# Output_v1_1.net
KiCad netlist of a schematic drawn in EAGLE
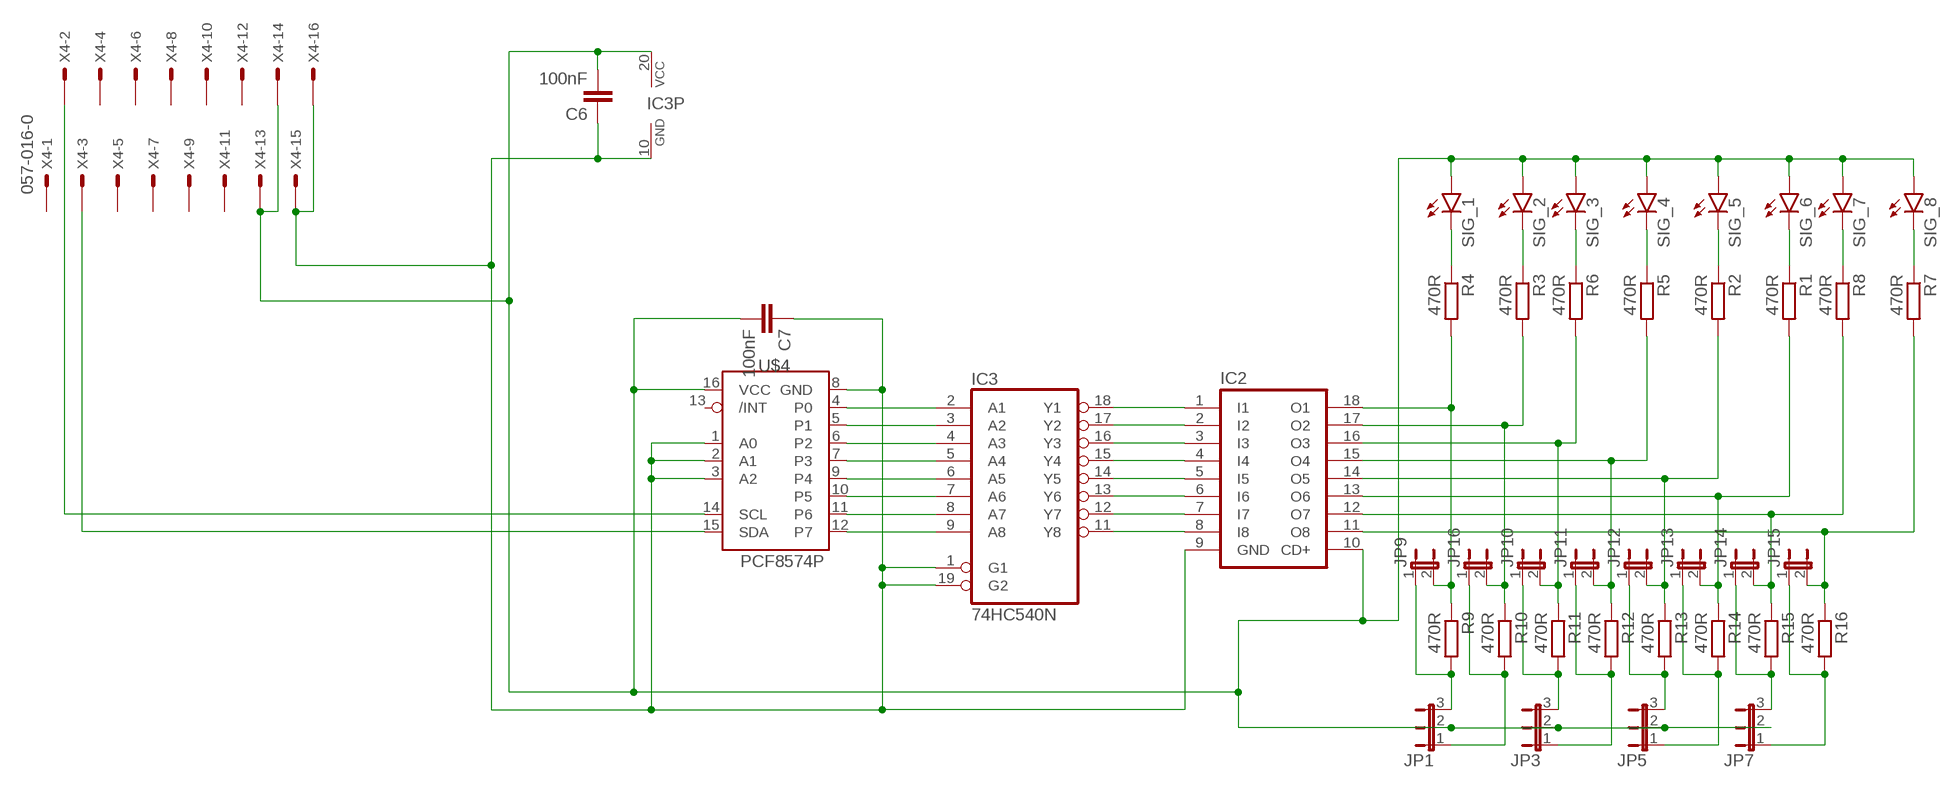
[diagram p0: schematic, sheet 1]

(export (version "E")
  (design (tool "Eeschema 10.0.6"))
  (components
    (comp (ref "C6")
      (value "100nF")
      (footprint "eagle-import:C025-024X044")
      (libsource (lib "eagle-import") (part "C-EU025-024X044"))
    )
    (comp (ref "C7")
      (value "100nF")
      (footprint "eagle-import:C025-024X044")
      (libsource (lib "eagle-import") (part "C-EU025-024X044"))
    )
    (comp (ref "IC2")
      (value "ULN2803A")
      (footprint "eagle-import:DIL18")
      (libsource (lib "eagle-import") (part "ULN2803A"))
    )
    (comp (ref "IC3")
      (value "74HC540N")
      (footprint "eagle-import:DIL20")
      (libsource (lib "eagle-import") (part "74540NHC"))
    )
    (comp (ref "JP1")
      (value "JP2E")
      (footprint "eagle-import:JP2")
      (libsource (lib "eagle-import") (part "JP2E"))
    )
    (comp (ref "JP3")
      (value "JP2E")
      (footprint "eagle-import:JP2")
      (libsource (lib "eagle-import") (part "JP2E"))
    )
    (comp (ref "JP5")
      (value "JP2E")
      (footprint "eagle-import:JP2")
      (libsource (lib "eagle-import") (part "JP2E"))
    )
    (comp (ref "JP7")
      (value "JP2E")
      (footprint "eagle-import:JP2")
      (libsource (lib "eagle-import") (part "JP2E"))
    )
    (comp (ref "JP9")
      (value "JP1E")
      (footprint "eagle-import:JP1")
      (libsource (lib "eagle-import") (part "JP1E"))
    )
    (comp (ref "JP10")
      (value "JP1E")
      (footprint "eagle-import:JP1")
      (libsource (lib "eagle-import") (part "JP1E"))
    )
    (comp (ref "JP11")
      (value "JP1E")
      (footprint "eagle-import:JP1")
      (libsource (lib "eagle-import") (part "JP1E"))
    )
    (comp (ref "JP12")
      (value "JP1E")
      (footprint "eagle-import:JP1")
      (libsource (lib "eagle-import") (part "JP1E"))
    )
    (comp (ref "JP13")
      (value "JP1E")
      (footprint "eagle-import:JP1")
      (libsource (lib "eagle-import") (part "JP1E"))
    )
    (comp (ref "JP14")
      (value "JP1E")
      (footprint "eagle-import:JP1")
      (libsource (lib "eagle-import") (part "JP1E"))
    )
    (comp (ref "JP15")
      (value "JP1E")
      (footprint "eagle-import:JP1")
      (libsource (lib "eagle-import") (part "JP1E"))
    )
    (comp (ref "JP16")
      (value "JP1E")
      (footprint "eagle-import:JP1")
      (libsource (lib "eagle-import") (part "JP1E"))
    )
    (comp (ref "R1")
      (value "470R")
      (footprint "eagle-import:0309_10")
      (libsource (lib "eagle-import") (part "R-EU_0309/10"))
    )
    (comp (ref "R2")
      (value "470R")
      (footprint "eagle-import:0309_10")
      (libsource (lib "eagle-import") (part "R-EU_0309/10"))
    )
    (comp (ref "R3")
      (value "470R")
      (footprint "eagle-import:0309_10")
      (libsource (lib "eagle-import") (part "R-EU_0309/10"))
    )
    (comp (ref "R4")
      (value "470R")
      (footprint "eagle-import:0309_10")
      (libsource (lib "eagle-import") (part "R-EU_0309/10"))
    )
    (comp (ref "R5")
      (value "470R")
      (footprint "eagle-import:0309_10")
      (libsource (lib "eagle-import") (part "R-EU_0309/10"))
    )
    (comp (ref "R6")
      (value "470R")
      (footprint "eagle-import:0309_10")
      (libsource (lib "eagle-import") (part "R-EU_0309/10"))
    )
    (comp (ref "R7")
      (value "470R")
      (footprint "eagle-import:0309_10")
      (libsource (lib "eagle-import") (part "R-EU_0309/10"))
    )
    (comp (ref "R8")
      (value "470R")
      (footprint "eagle-import:0309_10")
      (libsource (lib "eagle-import") (part "R-EU_0309/10"))
    )
    (comp (ref "R9")
      (value "470R")
      (footprint "eagle-import:0309_10")
      (libsource (lib "eagle-import") (part "R-EU_0309/10"))
    )
    (comp (ref "R10")
      (value "470R")
      (footprint "eagle-import:0309_10")
      (libsource (lib "eagle-import") (part "R-EU_0309/10"))
    )
    (comp (ref "R11")
      (value "470R")
      (footprint "eagle-import:0309_10")
      (libsource (lib "eagle-import") (part "R-EU_0309/10"))
    )
    (comp (ref "R12")
      (value "470R")
      (footprint "eagle-import:0309_10")
      (libsource (lib "eagle-import") (part "R-EU_0309/10"))
    )
    (comp (ref "R13")
      (value "470R")
      (footprint "eagle-import:0309_10")
      (libsource (lib "eagle-import") (part "R-EU_0309/10"))
    )
    (comp (ref "R14")
      (value "470R")
      (footprint "eagle-import:0309_10")
      (libsource (lib "eagle-import") (part "R-EU_0309/10"))
    )
    (comp (ref "R15")
      (value "470R")
      (footprint "eagle-import:0309_10")
      (libsource (lib "eagle-import") (part "R-EU_0309/10"))
    )
    (comp (ref "R16")
      (value "470R")
      (footprint "eagle-import:0309_10")
      (libsource (lib "eagle-import") (part "R-EU_0309/10"))
    )
    (comp (ref "SIG_1")
      (value "LED3MM")
      (footprint "eagle-import:LED3MM")
      (libsource (lib "eagle-import") (part "LED3MM"))
    )
    (comp (ref "SIG_2")
      (value "LED3MM")
      (footprint "eagle-import:LED3MM")
      (libsource (lib "eagle-import") (part "LED3MM"))
    )
    (comp (ref "SIG_3")
      (value "LED3MM")
      (footprint "eagle-import:LED3MM")
      (libsource (lib "eagle-import") (part "LED3MM"))
    )
    (comp (ref "SIG_4")
      (value "LED3MM")
      (footprint "eagle-import:LED3MM")
      (libsource (lib "eagle-import") (part "LED3MM"))
    )
    (comp (ref "SIG_5")
      (value "LED3MM")
      (footprint "eagle-import:LED3MM")
      (libsource (lib "eagle-import") (part "LED3MM"))
    )
    (comp (ref "SIG_6")
      (value "LED3MM")
      (footprint "eagle-import:LED3MM")
      (libsource (lib "eagle-import") (part "LED3MM"))
    )
    (comp (ref "SIG_7")
      (value "LED3MM")
      (footprint "eagle-import:LED3MM")
      (libsource (lib "eagle-import") (part "LED3MM"))
    )
    (comp (ref "SIG_8")
      (value "LED3MM")
      (footprint "eagle-import:LED3MM")
      (libsource (lib "eagle-import") (part "LED3MM"))
    )
    (comp (ref "U$4")
      (value "PCF8574P")
      (footprint "eagle-import:DIL16")
      (libsource (lib "eagle-import") (part "PCF8574P"))
    )
    (comp (ref "X4")
      (value "057-016-0")
      (footprint "eagle-import:057-016-0")
      (libsource (lib "eagle-import") (part "057-016-0"))
    )
  )
  (nets
    (net (code "1") (name "Net-(IC2-CD+)") (class "Default")
      (node (ref "C6") (pin "2") (pinfunction "2_2") (pintype "passive"))
      (node (ref "C7") (pin "2") (pinfunction "2_2") (pintype "passive"))
      (node (ref "IC2") (pin "10") (pinfunction "CD+_10") (pintype "passive"))
      (node (ref "IC3") (pin "20") (pinfunction "VCC_20") (pintype "power_in"))
      (node (ref "JP1") (pin "2") (pinfunction "2_2") (pintype "passive"))
      (node (ref "JP3") (pin "2") (pinfunction "2_2") (pintype "passive"))
      (node (ref "JP5") (pin "2") (pinfunction "2_2") (pintype "passive"))
      (node (ref "JP7") (pin "2") (pinfunction "2_2") (pintype "passive"))
      (node (ref "SIG_1") (pin "A") (pinfunction "A_A") (pintype "passive"))
      (node (ref "SIG_2") (pin "A") (pinfunction "A_A") (pintype "passive"))
      (node (ref "SIG_3") (pin "A") (pinfunction "A_A") (pintype "passive"))
      (node (ref "SIG_4") (pin "A") (pinfunction "A_A") (pintype "passive"))
      (node (ref "SIG_5") (pin "A") (pinfunction "A_A") (pintype "passive"))
      (node (ref "SIG_6") (pin "A") (pinfunction "A_A") (pintype "passive"))
      (node (ref "SIG_7") (pin "A") (pinfunction "A_A") (pintype "passive"))
      (node (ref "SIG_8") (pin "A") (pinfunction "A_A") (pintype "passive"))
      (node (ref "U$4") (pin "16") (pinfunction "VCC_16") (pintype "power_in"))
      (node (ref "X4") (pin "13") (pinfunction "S_13") (pintype "passive"))
      (node (ref "X4") (pin "14") (pinfunction "S_14") (pintype "passive"))
    )
    (net (code "2") (name "Net-(IC2-GND)") (class "Default")
      (node (ref "C6") (pin "1") (pinfunction "1_1") (pintype "passive"))
      (node (ref "C7") (pin "1") (pinfunction "1_1") (pintype "passive"))
      (node (ref "IC2") (pin "9") (pinfunction "GND_9") (pintype "power_in"))
      (node (ref "IC3") (pin "1") (pinfunction "G1_1") (pintype "input"))
      (node (ref "IC3") (pin "10") (pinfunction "GND_10") (pintype "power_in"))
      (node (ref "IC3") (pin "19") (pinfunction "G2_19") (pintype "input"))
      (node (ref "U$4") (pin "1") (pinfunction "A0_1") (pintype "input"))
      (node (ref "U$4") (pin "2") (pinfunction "A1_2") (pintype "input"))
      (node (ref "U$4") (pin "3") (pinfunction "A2_3") (pintype "input"))
      (node (ref "U$4") (pin "8") (pinfunction "GND_8") (pintype "power_in"))
      (node (ref "X4") (pin "15") (pinfunction "S_15") (pintype "passive"))
      (node (ref "X4") (pin "16") (pinfunction "S_16") (pintype "passive"))
    )
    (net (code "3") (name "Net-(IC2-I1)") (class "Default")
      (node (ref "IC2") (pin "1") (pinfunction "I1_1") (pintype "input"))
      (node (ref "IC3") (pin "18") (pinfunction "Y1_18") (pintype "tri_state"))
    )
    (net (code "4") (name "Net-(IC2-I2)") (class "Default")
      (node (ref "IC2") (pin "2") (pinfunction "I2_2") (pintype "input"))
      (node (ref "IC3") (pin "17") (pinfunction "Y2_17") (pintype "tri_state"))
    )
    (net (code "5") (name "Net-(IC2-I3)") (class "Default")
      (node (ref "IC2") (pin "3") (pinfunction "I3_3") (pintype "input"))
      (node (ref "IC3") (pin "16") (pinfunction "Y3_16") (pintype "tri_state"))
    )
    (net (code "6") (name "Net-(IC2-I4)") (class "Default")
      (node (ref "IC2") (pin "4") (pinfunction "I4_4") (pintype "input"))
      (node (ref "IC3") (pin "15") (pinfunction "Y4_15") (pintype "tri_state"))
    )
    (net (code "7") (name "Net-(IC2-I5)") (class "Default")
      (node (ref "IC2") (pin "5") (pinfunction "I5_5") (pintype "input"))
      (node (ref "IC3") (pin "14") (pinfunction "Y5_14") (pintype "tri_state"))
    )
    (net (code "8") (name "Net-(IC2-I6)") (class "Default")
      (node (ref "IC2") (pin "6") (pinfunction "I6_6") (pintype "input"))
      (node (ref "IC3") (pin "13") (pinfunction "Y6_13") (pintype "tri_state"))
    )
    (net (code "9") (name "Net-(IC2-I7)") (class "Default")
      (node (ref "IC2") (pin "7") (pinfunction "I7_7") (pintype "input"))
      (node (ref "IC3") (pin "12") (pinfunction "Y7_12") (pintype "tri_state"))
    )
    (net (code "10") (name "Net-(IC2-I8)") (class "Default")
      (node (ref "IC2") (pin "8") (pinfunction "I8_8") (pintype "input"))
      (node (ref "IC3") (pin "11") (pinfunction "Y8_11") (pintype "tri_state"))
    )
    (net (code "11") (name "Net-(IC2-O1)") (class "Default")
      (node (ref "IC2") (pin "18") (pinfunction "O1_18") (pintype "open_collector"))
      (node (ref "JP9") (pin "2") (pinfunction "2_2") (pintype "passive"))
      (node (ref "R4") (pin "2") (pinfunction "2_2") (pintype "passive"))
      (node (ref "R9") (pin "1") (pinfunction "1_1") (pintype "passive"))
    )
    (net (code "12") (name "Net-(IC2-O2)") (class "Default")
      (node (ref "IC2") (pin "17") (pinfunction "O2_17") (pintype "open_collector"))
      (node (ref "JP16") (pin "2") (pinfunction "2_2") (pintype "passive"))
      (node (ref "R10") (pin "1") (pinfunction "1_1") (pintype "passive"))
      (node (ref "R3") (pin "2") (pinfunction "2_2") (pintype "passive"))
    )
    (net (code "13") (name "Net-(IC2-O3)") (class "Default")
      (node (ref "IC2") (pin "16") (pinfunction "O3_16") (pintype "open_collector"))
      (node (ref "JP10") (pin "2") (pinfunction "2_2") (pintype "passive"))
      (node (ref "R11") (pin "1") (pinfunction "1_1") (pintype "passive"))
      (node (ref "R6") (pin "2") (pinfunction "2_2") (pintype "passive"))
    )
    (net (code "14") (name "Net-(IC2-O4)") (class "Default")
      (node (ref "IC2") (pin "15") (pinfunction "O4_15") (pintype "open_collector"))
      (node (ref "JP11") (pin "2") (pinfunction "2_2") (pintype "passive"))
      (node (ref "R12") (pin "1") (pinfunction "1_1") (pintype "passive"))
      (node (ref "R5") (pin "2") (pinfunction "2_2") (pintype "passive"))
    )
    (net (code "15") (name "Net-(IC2-O5)") (class "Default")
      (node (ref "IC2") (pin "14") (pinfunction "O5_14") (pintype "open_collector"))
      (node (ref "JP12") (pin "2") (pinfunction "2_2") (pintype "passive"))
      (node (ref "R13") (pin "1") (pinfunction "1_1") (pintype "passive"))
      (node (ref "R2") (pin "2") (pinfunction "2_2") (pintype "passive"))
    )
    (net (code "16") (name "Net-(IC2-O6)") (class "Default")
      (node (ref "IC2") (pin "13") (pinfunction "O6_13") (pintype "open_collector"))
      (node (ref "JP13") (pin "2") (pinfunction "2_2") (pintype "passive"))
      (node (ref "R1") (pin "2") (pinfunction "2_2") (pintype "passive"))
      (node (ref "R14") (pin "1") (pinfunction "1_1") (pintype "passive"))
    )
    (net (code "17") (name "Net-(IC2-O7)") (class "Default")
      (node (ref "IC2") (pin "12") (pinfunction "O7_12") (pintype "open_collector"))
      (node (ref "JP14") (pin "2") (pinfunction "2_2") (pintype "passive"))
      (node (ref "R15") (pin "1") (pinfunction "1_1") (pintype "passive"))
      (node (ref "R8") (pin "2") (pinfunction "2_2") (pintype "passive"))
    )
    (net (code "18") (name "Net-(IC2-O8)") (class "Default")
      (node (ref "IC2") (pin "11") (pinfunction "O8_11") (pintype "open_collector"))
      (node (ref "JP15") (pin "2") (pinfunction "2_2") (pintype "passive"))
      (node (ref "R16") (pin "1") (pinfunction "1_1") (pintype "passive"))
      (node (ref "R7") (pin "2") (pinfunction "2_2") (pintype "passive"))
    )
    (net (code "19") (name "Net-(IC3A-A1)") (class "Default")
      (node (ref "IC3") (pin "2") (pinfunction "A1_2") (pintype "input"))
      (node (ref "U$4") (pin "4") (pinfunction "P0_4") (pintype "bidirectional"))
    )
    (net (code "20") (name "Net-(IC3A-A2)") (class "Default")
      (node (ref "IC3") (pin "3") (pinfunction "A2_3") (pintype "input"))
      (node (ref "U$4") (pin "5") (pinfunction "P1_5") (pintype "bidirectional"))
    )
    (net (code "21") (name "Net-(IC3A-A3)") (class "Default")
      (node (ref "IC3") (pin "4") (pinfunction "A3_4") (pintype "input"))
      (node (ref "U$4") (pin "6") (pinfunction "P2_6") (pintype "bidirectional"))
    )
    (net (code "22") (name "Net-(IC3A-A4)") (class "Default")
      (node (ref "IC3") (pin "5") (pinfunction "A4_5") (pintype "input"))
      (node (ref "U$4") (pin "7") (pinfunction "P3_7") (pintype "bidirectional"))
    )
    (net (code "23") (name "Net-(IC3A-A5)") (class "Default")
      (node (ref "IC3") (pin "6") (pinfunction "A5_6") (pintype "input"))
      (node (ref "U$4") (pin "9") (pinfunction "P4_9") (pintype "bidirectional"))
    )
    (net (code "24") (name "Net-(IC3A-A6)") (class "Default")
      (node (ref "IC3") (pin "7") (pinfunction "A6_7") (pintype "input"))
      (node (ref "U$4") (pin "10") (pinfunction "P5_10") (pintype "bidirectional"))
    )
    (net (code "25") (name "Net-(IC3A-A7)") (class "Default")
      (node (ref "IC3") (pin "8") (pinfunction "A7_8") (pintype "input"))
      (node (ref "U$4") (pin "11") (pinfunction "P6_11") (pintype "bidirectional"))
    )
    (net (code "26") (name "Net-(IC3A-A8)") (class "Default")
      (node (ref "IC3") (pin "9") (pinfunction "A8_9") (pintype "input"))
      (node (ref "U$4") (pin "12") (pinfunction "P7_12") (pintype "bidirectional"))
    )
    (net (code "27") (name "Net-(JP1-Pad1)") (class "Default")
      (node (ref "JP1") (pin "1") (pinfunction "1_1") (pintype "passive"))
      (node (ref "JP16") (pin "1") (pinfunction "1_1") (pintype "passive"))
      (node (ref "R10") (pin "2") (pinfunction "2_2") (pintype "passive"))
    )
    (net (code "28") (name "Net-(JP1-Pad3)") (class "Default")
      (node (ref "JP1") (pin "3") (pinfunction "3_3") (pintype "passive"))
      (node (ref "JP9") (pin "1") (pinfunction "1_1") (pintype "passive"))
      (node (ref "R9") (pin "2") (pinfunction "2_2") (pintype "passive"))
    )
    (net (code "29") (name "Net-(JP10-Pad1)") (class "Default")
      (node (ref "JP10") (pin "1") (pinfunction "1_1") (pintype "passive"))
      (node (ref "JP3") (pin "3") (pinfunction "3_3") (pintype "passive"))
      (node (ref "R11") (pin "2") (pinfunction "2_2") (pintype "passive"))
    )
    (net (code "30") (name "Net-(JP11-Pad1)") (class "Default")
      (node (ref "JP11") (pin "1") (pinfunction "1_1") (pintype "passive"))
      (node (ref "JP3") (pin "1") (pinfunction "1_1") (pintype "passive"))
      (node (ref "R12") (pin "2") (pinfunction "2_2") (pintype "passive"))
    )
    (net (code "31") (name "Net-(JP12-Pad1)") (class "Default")
      (node (ref "JP12") (pin "1") (pinfunction "1_1") (pintype "passive"))
      (node (ref "JP5") (pin "3") (pinfunction "3_3") (pintype "passive"))
      (node (ref "R13") (pin "2") (pinfunction "2_2") (pintype "passive"))
    )
    (net (code "32") (name "Net-(JP13-Pad1)") (class "Default")
      (node (ref "JP13") (pin "1") (pinfunction "1_1") (pintype "passive"))
      (node (ref "JP5") (pin "1") (pinfunction "1_1") (pintype "passive"))
      (node (ref "R14") (pin "2") (pinfunction "2_2") (pintype "passive"))
    )
    (net (code "33") (name "Net-(JP14-Pad1)") (class "Default")
      (node (ref "JP14") (pin "1") (pinfunction "1_1") (pintype "passive"))
      (node (ref "JP7") (pin "3") (pinfunction "3_3") (pintype "passive"))
      (node (ref "R15") (pin "2") (pinfunction "2_2") (pintype "passive"))
    )
    (net (code "34") (name "Net-(JP15-Pad1)") (class "Default")
      (node (ref "JP15") (pin "1") (pinfunction "1_1") (pintype "passive"))
      (node (ref "JP7") (pin "1") (pinfunction "1_1") (pintype "passive"))
      (node (ref "R16") (pin "2") (pinfunction "2_2") (pintype "passive"))
    )
    (net (code "35") (name "Net-(SIG_1-C)") (class "Default")
      (node (ref "R4") (pin "1") (pinfunction "1_1") (pintype "passive"))
      (node (ref "SIG_1") (pin "K") (pinfunction "C_K") (pintype "passive"))
    )
    (net (code "36") (name "Net-(SIG_2-C)") (class "Default")
      (node (ref "R3") (pin "1") (pinfunction "1_1") (pintype "passive"))
      (node (ref "SIG_2") (pin "K") (pinfunction "C_K") (pintype "passive"))
    )
    (net (code "37") (name "Net-(SIG_3-C)") (class "Default")
      (node (ref "R6") (pin "1") (pinfunction "1_1") (pintype "passive"))
      (node (ref "SIG_3") (pin "K") (pinfunction "C_K") (pintype "passive"))
    )
    (net (code "38") (name "Net-(SIG_4-C)") (class "Default")
      (node (ref "R5") (pin "1") (pinfunction "1_1") (pintype "passive"))
      (node (ref "SIG_4") (pin "K") (pinfunction "C_K") (pintype "passive"))
    )
    (net (code "39") (name "Net-(SIG_5-C)") (class "Default")
      (node (ref "R2") (pin "1") (pinfunction "1_1") (pintype "passive"))
      (node (ref "SIG_5") (pin "K") (pinfunction "C_K") (pintype "passive"))
    )
    (net (code "40") (name "Net-(SIG_6-C)") (class "Default")
      (node (ref "R1") (pin "1") (pinfunction "1_1") (pintype "passive"))
      (node (ref "SIG_6") (pin "K") (pinfunction "C_K") (pintype "passive"))
    )
    (net (code "41") (name "Net-(SIG_7-C)") (class "Default")
      (node (ref "R8") (pin "1") (pinfunction "1_1") (pintype "passive"))
      (node (ref "SIG_7") (pin "K") (pinfunction "C_K") (pintype "passive"))
    )
    (net (code "42") (name "Net-(SIG_8-C)") (class "Default")
      (node (ref "R7") (pin "1") (pinfunction "1_1") (pintype "passive"))
      (node (ref "SIG_8") (pin "K") (pinfunction "C_K") (pintype "passive"))
    )
    (net (code "43") (name "Net-(U$4-SCL)") (class "Default")
      (node (ref "U$4") (pin "14") (pinfunction "SCL_14") (pintype "input"))
      (node (ref "X4") (pin "2") (pinfunction "S_2") (pintype "passive"))
    )
    (net (code "44") (name "Net-(U$4-SDA)") (class "Default")
      (node (ref "U$4") (pin "15") (pinfunction "SDA_15") (pintype "bidirectional"))
      (node (ref "X4") (pin "3") (pinfunction "S_3") (pintype "passive"))
    )
    (net (code "45") (name "unconnected-(U$4-{slash}INT-Pad13)") (class "Default")
      (node (ref "U$4") (pin "13") (pinfunction "/INT_13") (pintype "output"))
    )
    (net (code "46") (name "unconnected-(X4A-S-Pad1)") (class "Default")
      (node (ref "X4") (pin "1") (pinfunction "S_1") (pintype "passive"))
    )
    (net (code "47") (name "unconnected-(X4B-S-Pad10)") (class "Default")
      (node (ref "X4") (pin "10") (pinfunction "S_10") (pintype "passive"))
    )
    (net (code "48") (name "unconnected-(X4C-S-Pad11)") (class "Default")
      (node (ref "X4") (pin "11") (pinfunction "S_11") (pintype "passive"))
    )
    (net (code "49") (name "unconnected-(X4D-S-Pad12)") (class "Default")
      (node (ref "X4") (pin "12") (pinfunction "S_12") (pintype "passive"))
    )
    (net (code "50") (name "unconnected-(X4K-S-Pad4)") (class "Default")
      (node (ref "X4") (pin "4") (pinfunction "S_4") (pintype "passive"))
    )
    (net (code "51") (name "unconnected-(X4L-S-Pad5)") (class "Default")
      (node (ref "X4") (pin "5") (pinfunction "S_5") (pintype "passive"))
    )
    (net (code "52") (name "unconnected-(X4M-S-Pad6)") (class "Default")
      (node (ref "X4") (pin "6") (pinfunction "S_6") (pintype "passive"))
    )
    (net (code "53") (name "unconnected-(X4N-S-Pad7)") (class "Default")
      (node (ref "X4") (pin "7") (pinfunction "S_7") (pintype "passive"))
    )
    (net (code "54") (name "unconnected-(X4O-S-Pad8)") (class "Default")
      (node (ref "X4") (pin "8") (pinfunction "S_8") (pintype "passive"))
    )
    (net (code "55") (name "unconnected-(X4P-S-Pad9)") (class "Default")
      (node (ref "X4") (pin "9") (pinfunction "S_9") (pintype "passive"))
    )
  )
)
